# Sheet2.net
KiCad netlist of a schematic drawn in Altium Designer
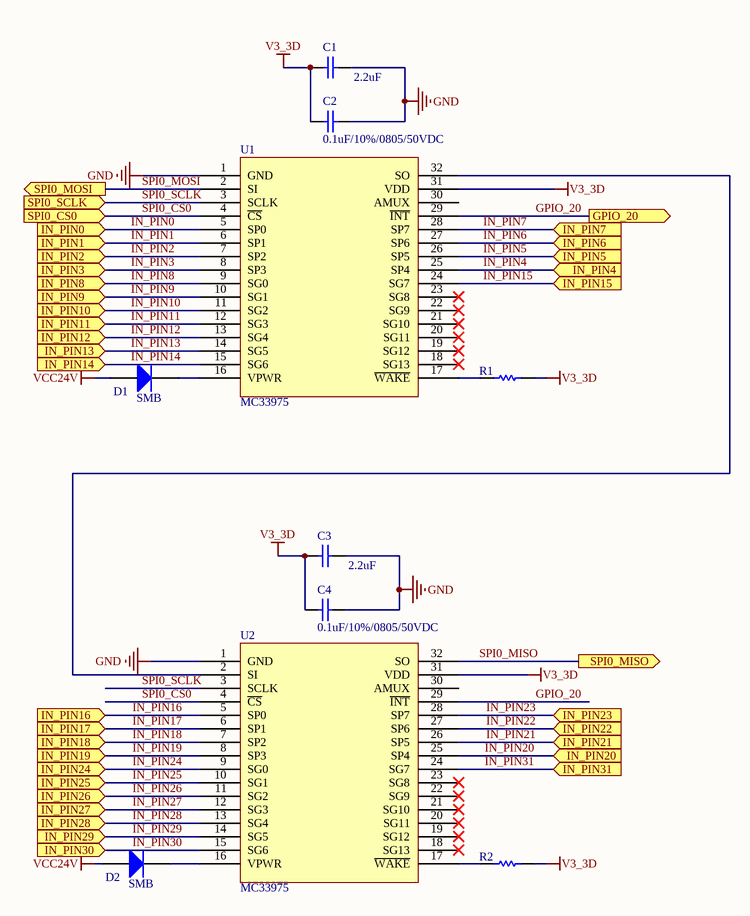
[diagram p0: Sheet2.SchDoc]

(export (version "E")
  (design (tool "Eeschema 10.0.6"))
  (components
    (comp (ref "C1")
      (value "2.2uF")
      (footprint "C-0805")
      (description "Capacitor")
      (fields (field (name "Comment") "Cap") (field (name "PUBLISHER") "Altium Limited"))
      (libsource (lib "Miscellaneous Devices") (part "Cap"))
    )
    (comp (ref "C2")
      (value "0.1uF/10%/0805/50VDC")
      (footprint "C-0805")
      (libsource (lib "浙江关西电机数据库") (part "CAP_Non-polarity"))
    )
    (comp (ref "C3")
      (value "2.2uF")
      (footprint "C-0805")
      (description "Capacitor")
      (fields (field (name "Comment") "Cap") (field (name "PUBLISHER") "Altium Limited"))
      (libsource (lib "Miscellaneous Devices") (part "Cap"))
    )
    (comp (ref "C4")
      (value "0.1uF/10%/0805/50VDC")
      (footprint "C-0805")
      (libsource (lib "浙江关西电机数据库") (part "CAP_Non-polarity"))
    )
    (comp (ref "D1")
      (value "SMB")
      (footprint "SMB")
      (description "3 Amp Medium Power Silicon Rectifier Diode")
      (fields (field (name "PUBLISHER") "Altium Limited"))
      (libsource (lib "Miscellaneous Devices") (part "Diode 1N5408"))
    )
    (comp (ref "D2")
      (value "SMB")
      (footprint "SMB")
      (description "3 Amp Medium Power Silicon Rectifier Diode")
      (fields (field (name "PUBLISHER") "Altium Limited"))
      (libsource (lib "Miscellaneous Devices") (part "Diode 1N5408"))
    )
    (comp (ref "R1")
      (value "10K/1%/0805/1/8W")
      (footprint "R-0805")
      (fields (field (name "PART NUMBER") "ASR-0028BA"))
      (libsource (lib "浙江关西电机数据库") (part "RES_1"))
    )
    (comp (ref "R2")
      (value "10K/1%/0805/1/8W")
      (footprint "R-0805")
      (fields (field (name "PART NUMBER") "ASR-0028BA"))
      (libsource (lib "浙江关西电机数据库") (part "RES_1"))
    )
    (comp (ref "U1")
      (value "MC33975")
      (footprint "SOIC-32")
      (libsource (lib "SCHLIBRARIES") (part "MC33975"))
    )
    (comp (ref "U2")
      (value "MC33975")
      (footprint "SOIC-32")
      (libsource (lib "SCHLIBRARIES") (part "MC33975"))
    )
  )
  (nets
    (net (code "1") (name "/GPIO_20") (class "Default")
      (node (ref "U1") (pin "29") (pinfunction "~{INT}_29") (pintype "passive"))
      (node (ref "U2") (pin "29") (pinfunction "~{INT}_29") (pintype "passive"))
    )
    (net (code "2") (name "/IN_PIN0") (class "Default")
      (node (ref "U1") (pin "5") (pinfunction "SP0_5") (pintype "passive"))
    )
    (net (code "3") (name "/IN_PIN1") (class "Default")
      (node (ref "U1") (pin "6") (pinfunction "SP1_6") (pintype "passive"))
    )
    (net (code "4") (name "/IN_PIN2") (class "Default")
      (node (ref "U1") (pin "7") (pinfunction "SP2_7") (pintype "passive"))
    )
    (net (code "5") (name "/IN_PIN3") (class "Default")
      (node (ref "U1") (pin "8") (pinfunction "SP3_8") (pintype "passive"))
    )
    (net (code "6") (name "/IN_PIN4") (class "Default")
      (node (ref "U1") (pin "25") (pinfunction "SP4_25") (pintype "passive"))
    )
    (net (code "7") (name "/IN_PIN5") (class "Default")
      (node (ref "U1") (pin "26") (pinfunction "SP5_26") (pintype "passive"))
    )
    (net (code "8") (name "/IN_PIN6") (class "Default")
      (node (ref "U1") (pin "27") (pinfunction "SP6_27") (pintype "passive"))
    )
    (net (code "9") (name "/IN_PIN7") (class "Default")
      (node (ref "U1") (pin "28") (pinfunction "SP7_28") (pintype "passive"))
    )
    (net (code "10") (name "/IN_PIN8") (class "Default")
      (node (ref "U1") (pin "9") (pinfunction "SG0_9") (pintype "passive"))
    )
    (net (code "11") (name "/IN_PIN9") (class "Default")
      (node (ref "U1") (pin "10") (pinfunction "SG1_10") (pintype "passive"))
    )
    (net (code "12") (name "/IN_PIN10") (class "Default")
      (node (ref "U1") (pin "11") (pinfunction "SG2_11") (pintype "passive"))
    )
    (net (code "13") (name "/IN_PIN11") (class "Default")
      (node (ref "U1") (pin "12") (pinfunction "SG3_12") (pintype "passive"))
    )
    (net (code "14") (name "/IN_PIN12") (class "Default")
      (node (ref "U1") (pin "13") (pinfunction "SG4_13") (pintype "passive"))
    )
    (net (code "15") (name "/IN_PIN13") (class "Default")
      (node (ref "U1") (pin "14") (pinfunction "SG5_14") (pintype "passive"))
    )
    (net (code "16") (name "/IN_PIN14") (class "Default")
      (node (ref "U1") (pin "15") (pinfunction "SG6_15") (pintype "passive"))
    )
    (net (code "17") (name "/IN_PIN15") (class "Default")
      (node (ref "U1") (pin "24") (pinfunction "SG7_24") (pintype "passive"))
    )
    (net (code "18") (name "/IN_PIN16") (class "Default")
      (node (ref "U2") (pin "5") (pinfunction "SP0_5") (pintype "passive"))
    )
    (net (code "19") (name "/IN_PIN17") (class "Default")
      (node (ref "U2") (pin "6") (pinfunction "SP1_6") (pintype "passive"))
    )
    (net (code "20") (name "/IN_PIN18") (class "Default")
      (node (ref "U2") (pin "7") (pinfunction "SP2_7") (pintype "passive"))
    )
    (net (code "21") (name "/IN_PIN19") (class "Default")
      (node (ref "U2") (pin "8") (pinfunction "SP3_8") (pintype "passive"))
    )
    (net (code "22") (name "/IN_PIN20") (class "Default")
      (node (ref "U2") (pin "25") (pinfunction "SP4_25") (pintype "passive"))
    )
    (net (code "23") (name "/IN_PIN21") (class "Default")
      (node (ref "U2") (pin "26") (pinfunction "SP5_26") (pintype "passive"))
    )
    (net (code "24") (name "/IN_PIN22") (class "Default")
      (node (ref "U2") (pin "27") (pinfunction "SP6_27") (pintype "passive"))
    )
    (net (code "25") (name "/IN_PIN23") (class "Default")
      (node (ref "U2") (pin "28") (pinfunction "SP7_28") (pintype "passive"))
    )
    (net (code "26") (name "/IN_PIN24") (class "Default")
      (node (ref "U2") (pin "9") (pinfunction "SG0_9") (pintype "passive"))
    )
    (net (code "27") (name "/IN_PIN25") (class "Default")
      (node (ref "U2") (pin "10") (pinfunction "SG1_10") (pintype "passive"))
    )
    (net (code "28") (name "/IN_PIN26") (class "Default")
      (node (ref "U2") (pin "11") (pinfunction "SG2_11") (pintype "passive"))
    )
    (net (code "29") (name "/IN_PIN27") (class "Default")
      (node (ref "U2") (pin "12") (pinfunction "SG3_12") (pintype "passive"))
    )
    (net (code "30") (name "/IN_PIN28") (class "Default")
      (node (ref "U2") (pin "13") (pinfunction "SG4_13") (pintype "passive"))
    )
    (net (code "31") (name "/IN_PIN29") (class "Default")
      (node (ref "U2") (pin "14") (pinfunction "SG5_14") (pintype "passive"))
    )
    (net (code "32") (name "/IN_PIN30") (class "Default")
      (node (ref "U2") (pin "15") (pinfunction "SG6_15") (pintype "passive"))
    )
    (net (code "33") (name "/IN_PIN31") (class "Default")
      (node (ref "U2") (pin "24") (pinfunction "SG7_24") (pintype "passive"))
    )
    (net (code "34") (name "/SPI0_CS0") (class "Default")
      (node (ref "U1") (pin "4") (pinfunction "~{CS}_4") (pintype "passive"))
      (node (ref "U2") (pin "4") (pinfunction "~{CS}_4") (pintype "passive"))
    )
    (net (code "35") (name "/SPI0_MISO") (class "Default")
      (node (ref "U2") (pin "32") (pinfunction "SO_32") (pintype "passive"))
    )
    (net (code "36") (name "/SPI0_MOSI") (class "Default")
      (node (ref "U1") (pin "2") (pinfunction "SI_2") (pintype "passive"))
    )
    (net (code "37") (name "/SPI0_SCLK") (class "Default")
      (node (ref "U1") (pin "3") (pinfunction "SCLK_3") (pintype "passive"))
      (node (ref "U2") (pin "3") (pinfunction "SCLK_3") (pintype "passive"))
    )
    (net (code "38") (name "GND") (class "Default")
      (node (ref "C1") (pin "1") (pinfunction "1_1") (pintype "passive"))
      (node (ref "C2") (pin "1") (pinfunction "1_1") (pintype "passive"))
      (node (ref "C3") (pin "1") (pinfunction "1_1") (pintype "passive"))
      (node (ref "C4") (pin "1") (pinfunction "1_1") (pintype "passive"))
      (node (ref "U1") (pin "1") (pinfunction "GND_1") (pintype "passive"))
      (node (ref "U2") (pin "1") (pinfunction "GND_1") (pintype "passive"))
    )
    (net (code "39") (name "Net-(D1-K)") (class "Default")
      (node (ref "D1") (pin "2") (pinfunction "K_2") (pintype "passive"))
      (node (ref "U1") (pin "16") (pinfunction "VPWR_16") (pintype "passive"))
    )
    (net (code "40") (name "Net-(D2-K)") (class "Default")
      (node (ref "D2") (pin "2") (pinfunction "K_2") (pintype "passive"))
      (node (ref "U2") (pin "16") (pinfunction "VPWR_16") (pintype "passive"))
    )
    (net (code "41") (name "Net-(U1-SO)") (class "Default")
      (node (ref "U1") (pin "32") (pinfunction "SO_32") (pintype "passive"))
      (node (ref "U2") (pin "2") (pinfunction "SI_2") (pintype "passive"))
    )
    (net (code "42") (name "Net-(U1-~{WAKE})") (class "Default")
      (node (ref "R1") (pin "2") (pinfunction "2_2") (pintype "passive"))
      (node (ref "U1") (pin "17") (pinfunction "~{WAKE}_17") (pintype "passive"))
    )
    (net (code "43") (name "Net-(U2-~{WAKE})") (class "Default")
      (node (ref "R2") (pin "2") (pinfunction "2_2") (pintype "passive"))
      (node (ref "U2") (pin "17") (pinfunction "~{WAKE}_17") (pintype "passive"))
    )
    (net (code "44") (name "V3_3D") (class "Default")
      (node (ref "C1") (pin "2") (pinfunction "2_2") (pintype "passive"))
      (node (ref "C2") (pin "2") (pinfunction "2_2") (pintype "passive"))
      (node (ref "C3") (pin "2") (pinfunction "2_2") (pintype "passive"))
      (node (ref "C4") (pin "2") (pinfunction "2_2") (pintype "passive"))
      (node (ref "R1") (pin "1") (pinfunction "1_1") (pintype "passive"))
      (node (ref "R2") (pin "1") (pinfunction "1_1") (pintype "passive"))
      (node (ref "U1") (pin "31") (pinfunction "VDD_31") (pintype "passive"))
      (node (ref "U2") (pin "31") (pinfunction "VDD_31") (pintype "passive"))
    )
    (net (code "45") (name "VCC24V") (class "Default")
      (node (ref "D1") (pin "1") (pinfunction "A_1") (pintype "passive"))
      (node (ref "D2") (pin "1") (pinfunction "A_1") (pintype "passive"))
    )
    (net (code "46") (name "unconnected-(U1-AMUX-Pad30)") (class "Default")
      (node (ref "U1") (pin "30") (pinfunction "AMUX_30") (pintype "passive"))
    )
    (net (code "47") (name "unconnected-(U1-SG8-Pad23)") (class "Default")
      (node (ref "U1") (pin "23") (pinfunction "SG8_23") (pintype "passive+no_connect"))
    )
    (net (code "48") (name "unconnected-(U1-SG9-Pad22)") (class "Default")
      (node (ref "U1") (pin "22") (pinfunction "SG9_22") (pintype "passive+no_connect"))
    )
    (net (code "49") (name "unconnected-(U1-SG10-Pad21)") (class "Default")
      (node (ref "U1") (pin "21") (pinfunction "SG10_21") (pintype "passive+no_connect"))
    )
    (net (code "50") (name "unconnected-(U1-SG11-Pad20)") (class "Default")
      (node (ref "U1") (pin "20") (pinfunction "SG11_20") (pintype "passive+no_connect"))
    )
    (net (code "51") (name "unconnected-(U1-SG12-Pad19)") (class "Default")
      (node (ref "U1") (pin "19") (pinfunction "SG12_19") (pintype "passive+no_connect"))
    )
    (net (code "52") (name "unconnected-(U1-SG13-Pad18)") (class "Default")
      (node (ref "U1") (pin "18") (pinfunction "SG13_18") (pintype "passive+no_connect"))
    )
    (net (code "53") (name "unconnected-(U2-AMUX-Pad30)") (class "Default")
      (node (ref "U2") (pin "30") (pinfunction "AMUX_30") (pintype "passive"))
    )
    (net (code "54") (name "unconnected-(U2-SG8-Pad23)") (class "Default")
      (node (ref "U2") (pin "23") (pinfunction "SG8_23") (pintype "passive+no_connect"))
    )
    (net (code "55") (name "unconnected-(U2-SG9-Pad22)") (class "Default")
      (node (ref "U2") (pin "22") (pinfunction "SG9_22") (pintype "passive+no_connect"))
    )
    (net (code "56") (name "unconnected-(U2-SG10-Pad21)") (class "Default")
      (node (ref "U2") (pin "21") (pinfunction "SG10_21") (pintype "passive+no_connect"))
    )
    (net (code "57") (name "unconnected-(U2-SG11-Pad20)") (class "Default")
      (node (ref "U2") (pin "20") (pinfunction "SG11_20") (pintype "passive+no_connect"))
    )
    (net (code "58") (name "unconnected-(U2-SG12-Pad19)") (class "Default")
      (node (ref "U2") (pin "19") (pinfunction "SG12_19") (pintype "passive+no_connect"))
    )
    (net (code "59") (name "unconnected-(U2-SG13-Pad18)") (class "Default")
      (node (ref "U2") (pin "18") (pinfunction "SG13_18") (pintype "passive+no_connect"))
    )
  )
)
